# attiny_rc_switch_th.net
KiCad netlist of a schematic drawn in EAGLE
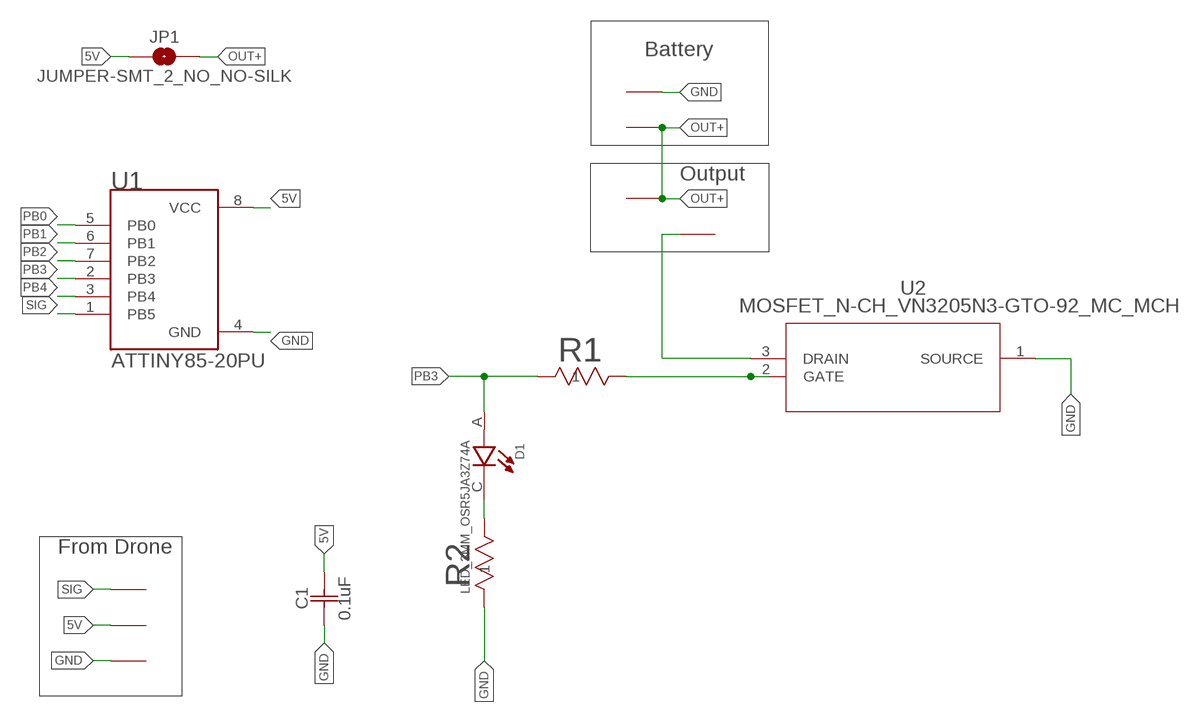
[diagram p0: schematic, sheet 1]

(export (version "E")
  (design (tool "Eeschema 10.0.6"))
  (components
    (comp (ref "C1")
      (value "0.1uF")
      (footprint "eagle-import:K10XK10X7RF5UH5")
      (fields
        (field (name "MANUFACTURER_PART_NUMBER") "K103K10X7RF5UH5")
        (field (name "COPYRIGHT") "Copyright (C) 2024 Ultra Librarian. All rights reserved.")
      )
      (libsource (lib "eagle-import") (part "CAPACITOR_CERAMIC_50V_K10XK10X7RF5UH5K103K10X7RF5UH5_VIS"))
    )
    (comp (ref "D1")
      (value "LED_3MM_OSR5JA3Z74A")
      (footprint "eagle-import:OSR5JA3Z74A")
      (fields (field (name "MF") "optosupply") (field (name "MP") "OSR5JA3Z74A"))
      (libsource (lib "eagle-import") (part "LED_3MM_OSR5JA3Z74A"))
    )
    (comp (ref "JP1")
      (value "JUMPER-SMT_2_NO_NO-SILK")
      (footprint "eagle-import:SMT-JUMPER_2_NO_NO-SILK")
      (libsource (lib "eagle-import") (part "JUMPER-SMT_2_NO_NO-SILK"))
    )
    (comp (ref "R1")
      (value "RESISTOR_1/8W_CF18JTSTA_CF18_STP")
      (footprint "eagle-import:RESISTOR_1_8W_CF18JT")
      (fields
        (field (name "MANUFACTURER_PART_NUMBER") "CF18JT100K")
        (field (name "COPYRIGHT") "Copyright (C) 2025 Ultra Librarian. All rights reserved.")
      )
      (libsource (lib "eagle-import") (part "RESISTOR_1/8W_CF18JTSTA_CF18_STP"))
    )
    (comp (ref "R2")
      (value "RESISTOR_1/8W_CF18JTSTA_CF18_STP")
      (footprint "eagle-import:RESISTOR_1_8W_CF18JT")
      (fields
        (field (name "MANUFACTURER_PART_NUMBER") "CF18JT100K")
        (field (name "COPYRIGHT") "Copyright (C) 2025 Ultra Librarian. All rights reserved.")
      )
      (libsource (lib "eagle-import") (part "RESISTOR_1/8W_CF18JTSTA_CF18_STP"))
    )
    (comp (ref "U$1")
      (value "SMD_PAD")
      (footprint "eagle-import:SMD_PAD")
      (libsource (lib "eagle-import") (part "SMD_PAD"))
    )
    (comp (ref "U$2")
      (value "SMD_PAD")
      (footprint "eagle-import:SMD_PAD")
      (libsource (lib "eagle-import") (part "SMD_PAD"))
    )
    (comp (ref "U$3")
      (value "SMD_PAD")
      (footprint "eagle-import:SMD_PAD")
      (libsource (lib "eagle-import") (part "SMD_PAD"))
    )
    (comp (ref "U$4")
      (value "SMD_PAD")
      (footprint "eagle-import:SMD_PAD")
      (libsource (lib "eagle-import") (part "SMD_PAD"))
    )
    (comp (ref "U$5")
      (value "SMD_PAD")
      (footprint "eagle-import:SMD_PAD")
      (libsource (lib "eagle-import") (part "SMD_PAD"))
    )
    (comp (ref "U$6")
      (value "SMD_PAD")
      (footprint "eagle-import:SMD_PAD")
      (libsource (lib "eagle-import") (part "SMD_PAD"))
    )
    (comp (ref "U$8")
      (value "SMD_PAD")
      (footprint "eagle-import:SMD_PAD")
      (libsource (lib "eagle-import") (part "SMD_PAD"))
    )
    (comp (ref "U1")
      (value "ATTINY85-20PU")
      (footprint "eagle-import:ATTINY85-20PU")
      (fields (field (name "MANUFACTURER") "Atmel "))
      (libsource (lib "eagle-import") (part "ATTINY85-20PU"))
    )
    (comp (ref "U2")
      (value "MOSFET_N-CH_VN3205N3-GTO-92_MC_MCH")
      (footprint "eagle-import:MOSFET_N-CH_VN3205N3-G")
      (fields
        (field (name "MANUFACTURER_PART_NUMBER") "VN3205N3-G")
        (field (name "COPYRIGHT") "Copyright (C) 2025 Ultra Librarian. All rights reserved.")
      )
      (libsource (lib "eagle-import") (part "MOSFET_N-CH_VN3205N3-GTO-92_MC_MCH"))
    )
  )
  (nets
    (net (code "1") (name "5V") (class "Default")
      (node (ref "C1") (pin "2") (pinfunction "2_2") (pintype "passive"))
      (node (ref "JP1") (pin "1") (pinfunction "1_1") (pintype "passive"))
      (node (ref "U$1") (pin "P$1") (pinfunction "P$1_P$1") (pintype "bidirectional"))
      (node (ref "U1") (pin "8") (pinfunction "VCC_8") (pintype "power_in"))
    )
    (net (code "2") (name "GND") (class "Default")
      (node (ref "C1") (pin "1") (pinfunction "1_1") (pintype "passive"))
      (node (ref "R2") (pin "1") (pinfunction "1_1") (pintype "passive"))
      (node (ref "U$2") (pin "P$1") (pinfunction "P$1_P$1") (pintype "bidirectional"))
      (node (ref "U$4") (pin "P$1") (pinfunction "P$1_P$1") (pintype "bidirectional"))
      (node (ref "U1") (pin "4") (pinfunction "GND_4") (pintype "power_in"))
      (node (ref "U2") (pin "1") (pinfunction "SOURCE_1") (pintype "passive"))
    )
    (net (code "3") (name "Net-(D1-PadC)") (class "Default")
      (node (ref "D1") (pin "C") (pinfunction "C_C") (pintype "passive"))
      (node (ref "R2") (pin "2") (pinfunction "2_2") (pintype "passive"))
    )
    (net (code "4") (name "Net-(U2-DRAIN)") (class "Default")
      (node (ref "U$6") (pin "P$1") (pinfunction "P$1_P$1") (pintype "bidirectional"))
      (node (ref "U2") (pin "3") (pinfunction "DRAIN_3") (pintype "passive"))
    )
    (net (code "5") (name "Net-(U2-GATE)") (class "Default")
      (node (ref "R1") (pin "2") (pinfunction "2_2") (pintype "passive"))
      (node (ref "U2") (pin "2") (pinfunction "GATE_2") (pintype "passive"))
    )
    (net (code "6") (name "OUT+") (class "Default")
      (node (ref "JP1") (pin "2") (pinfunction "2_2") (pintype "passive"))
      (node (ref "U$3") (pin "P$1") (pinfunction "P$1_P$1") (pintype "bidirectional"))
      (node (ref "U$5") (pin "P$1") (pinfunction "P$1_P$1") (pintype "bidirectional"))
    )
    (net (code "7") (name "PB0") (class "Default")
      (node (ref "U1") (pin "5") (pinfunction "PB0_5") (pintype "bidirectional"))
    )
    (net (code "8") (name "PB1") (class "Default")
      (node (ref "U1") (pin "6") (pinfunction "PB1_6") (pintype "bidirectional"))
    )
    (net (code "9") (name "PB2") (class "Default")
      (node (ref "U1") (pin "7") (pinfunction "PB2_7") (pintype "bidirectional"))
    )
    (net (code "10") (name "PB3") (class "Default")
      (node (ref "D1") (pin "A") (pinfunction "A_A") (pintype "passive"))
      (node (ref "R1") (pin "1") (pinfunction "1_1") (pintype "passive"))
      (node (ref "U1") (pin "2") (pinfunction "PB3_2") (pintype "bidirectional"))
    )
    (net (code "11") (name "PB4") (class "Default")
      (node (ref "U1") (pin "3") (pinfunction "PB4_3") (pintype "bidirectional"))
    )
    (net (code "12") (name "SIG") (class "Default")
      (node (ref "U$8") (pin "P$1") (pinfunction "P$1_P$1") (pintype "bidirectional"))
      (node (ref "U1") (pin "1") (pinfunction "PB5_1") (pintype "bidirectional"))
    )
  )
)
